# Sheet1.net
KiCad netlist of a schematic drawn in Altium Designer
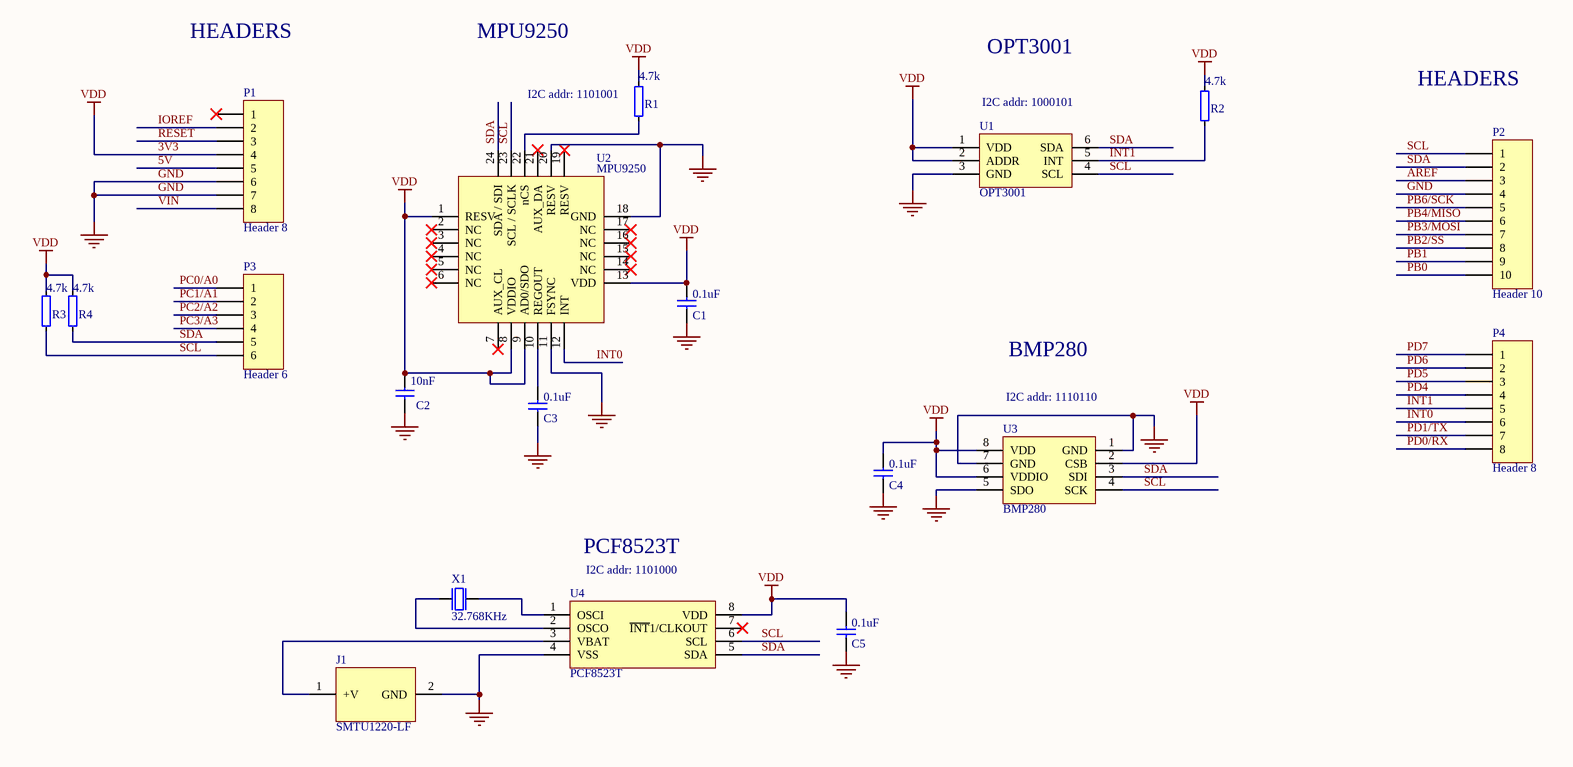
[diagram p0: Sheet1.SchDoc]

(export (version "E")
  (design (tool "Eeschema 10.0.6"))
  (components
    (comp (ref "C1") (value "0.1uF") (footprint "CAPC1608X06L") (libsource (lib "Schlib1") (part "CAP_0603")))
    (comp (ref "C2") (value "10nF") (footprint "CAPC1608X06L") (libsource (lib "Schlib1") (part "CAP_0603")))
    (comp (ref "C3") (value "0.1uF") (footprint "CAPC1608X06L") (libsource (lib "Schlib1") (part "CAP_0603")))
    (comp (ref "C4") (value "0.1uF") (footprint "CAPC1608X06L") (libsource (lib "Schlib1") (part "CAP_0603")))
    (comp (ref "C5") (value "0.1uF") (footprint "CAPC1608X06L") (libsource (lib "Schlib1") (part "CAP_0603")))
    (comp (ref "J1")
      (value "SMTU1220-LF")
      (footprint "SMTU1220-LF")
      (libsource (lib "Schlib1") (part "COIN_CELL"))
    )
    (comp (ref "P1")
      (value "Header 8")
      (footprint "HDR1X8")
      (description "Header, 8-Pin")
      (fields (field (name "PUBLISHER") "Altium Limited"))
      (libsource (lib "Miscellaneous Connectors") (part "Header 8"))
    )
    (comp (ref "P2")
      (value "Header 10")
      (footprint "HDR1X10")
      (description "Header, 10-Pin")
      (fields (field (name "PUBLISHER") "Altium Limited"))
      (libsource (lib "Miscellaneous Connectors") (part "Header 10"))
    )
    (comp (ref "P3")
      (value "Header 6")
      (footprint "HDR1X6")
      (description "Header, 6-Pin")
      (fields (field (name "PUBLISHER") "Altium Limited"))
      (libsource (lib "Miscellaneous Connectors") (part "Header 6"))
    )
    (comp (ref "P4")
      (value "Header 8")
      (footprint "HDR1X8")
      (description "Header, 8-Pin")
      (fields (field (name "PUBLISHER") "Altium Limited"))
      (libsource (lib "Miscellaneous Connectors") (part "Header 8"))
    )
    (comp (ref "R1") (value "4.7k") (footprint "RESC1608X06N") (libsource (lib "Schlib1") (part "RES_0603")))
    (comp (ref "R2") (value "4.7k") (footprint "RESC1608X06N") (libsource (lib "Schlib1") (part "RES_0603")))
    (comp (ref "R3") (value "4.7k") (footprint "RESC1608X06N") (libsource (lib "Schlib1") (part "RES_0603")))
    (comp (ref "R4") (value "4.7k") (footprint "RESC1608X06N") (libsource (lib "Schlib1") (part "RES_0603")))
    (comp (ref "U1")
      (value "OPT3001")
      (footprint "SON65P200X65_HS-7N")
      (libsource (lib "Schlib1") (part "OPT3001"))
    )
    (comp (ref "U2")
      (value "MPU9250")
      (footprint "QFN40P300X300X105_HS-25N")
      (libsource (lib "Schlib1") (part "MPU9250"))
    )
    (comp (ref "U3")
      (value "BMP280")
      (footprint "SON65P200X100-8N")
      (libsource (lib "Schlib1") (part "BMP280"))
    )
    (comp (ref "U4")
      (value "PCF8523T")
      (footprint "SOIC127P600X175-8N")
      (libsource (lib "Schlib1") (part "PCF8523T"))
    )
    (comp (ref "X1")
      (value "32.768KHz")
      (footprint "XTAL_3215")
      (description "32.768KHZ ±20PPM,9.0PF - CRYSTAL, SM, WATCH")
      (libsource (lib "Schlib1") (part "XTAL_3215"))
    )
  )
  (nets
    (net (code "1") (name "/5V") (class "Default")
      (node (ref "P1") (pin "5") (pinfunction "5_5") (pintype "passive"))
    )
    (net (code "2") (name "/AREF") (class "Default")
      (node (ref "P2") (pin "3") (pinfunction "3_3") (pintype "passive"))
    )
    (net (code "3") (name "/INT0") (class "Default")
      (node (ref "P4") (pin "6") (pinfunction "6_6") (pintype "passive"))
      (node (ref "U2") (pin "12") (pinfunction "INT_12") (pintype "passive"))
    )
    (net (code "4") (name "/INT1") (class "Default")
      (node (ref "P4") (pin "5") (pinfunction "5_5") (pintype "passive"))
      (node (ref "R2") (pin "1") (pinfunction "1_1") (pintype "passive"))
      (node (ref "U1") (pin "5") (pinfunction "INT_5") (pintype "passive"))
    )
    (net (code "5") (name "/IOREF") (class "Default")
      (node (ref "P1") (pin "2") (pinfunction "2_2") (pintype "passive"))
    )
    (net (code "6") (name "/PB0") (class "Default")
      (node (ref "P2") (pin "10") (pinfunction "10_10") (pintype "passive"))
    )
    (net (code "7") (name "/PB1") (class "Default")
      (node (ref "P2") (pin "9") (pinfunction "9_9") (pintype "passive"))
    )
    (net (code "8") (name "/PB2{slash}SS") (class "Default")
      (node (ref "P2") (pin "8") (pinfunction "8_8") (pintype "passive"))
    )
    (net (code "9") (name "/PB3{slash}MOSI") (class "Default")
      (node (ref "P2") (pin "7") (pinfunction "7_7") (pintype "passive"))
    )
    (net (code "10") (name "/PB4{slash}MISO") (class "Default")
      (node (ref "P2") (pin "6") (pinfunction "6_6") (pintype "passive"))
    )
    (net (code "11") (name "/PB6{slash}SCK") (class "Default")
      (node (ref "P2") (pin "5") (pinfunction "5_5") (pintype "passive"))
    )
    (net (code "12") (name "/PC0{slash}A0") (class "Default")
      (node (ref "P3") (pin "1") (pinfunction "1_1") (pintype "passive"))
    )
    (net (code "13") (name "/PC1{slash}A1") (class "Default")
      (node (ref "P3") (pin "2") (pinfunction "2_2") (pintype "passive"))
    )
    (net (code "14") (name "/PC2{slash}A2") (class "Default")
      (node (ref "P3") (pin "3") (pinfunction "3_3") (pintype "passive"))
    )
    (net (code "15") (name "/PC3{slash}A3") (class "Default")
      (node (ref "P3") (pin "4") (pinfunction "4_4") (pintype "passive"))
    )
    (net (code "16") (name "/PD0{slash}RX") (class "Default")
      (node (ref "P4") (pin "8") (pinfunction "8_8") (pintype "passive"))
    )
    (net (code "17") (name "/PD1{slash}TX") (class "Default")
      (node (ref "P4") (pin "7") (pinfunction "7_7") (pintype "passive"))
    )
    (net (code "18") (name "/PD4") (class "Default")
      (node (ref "P4") (pin "4") (pinfunction "4_4") (pintype "passive"))
    )
    (net (code "19") (name "/PD5") (class "Default")
      (node (ref "P4") (pin "3") (pinfunction "3_3") (pintype "passive"))
    )
    (net (code "20") (name "/PD6") (class "Default")
      (node (ref "P4") (pin "2") (pinfunction "2_2") (pintype "passive"))
    )
    (net (code "21") (name "/PD7") (class "Default")
      (node (ref "P4") (pin "1") (pinfunction "1_1") (pintype "passive"))
    )
    (net (code "22") (name "/RESET") (class "Default")
      (node (ref "P1") (pin "3") (pinfunction "3_3") (pintype "passive"))
    )
    (net (code "23") (name "/SCL") (class "Default")
      (node (ref "P2") (pin "1") (pinfunction "1_1") (pintype "passive"))
      (node (ref "P3") (pin "6") (pinfunction "6_6") (pintype "passive"))
      (node (ref "R3") (pin "1") (pinfunction "1_1") (pintype "passive"))
      (node (ref "U1") (pin "4") (pinfunction "SCL_4") (pintype "passive"))
      (node (ref "U2") (pin "23") (pinfunction "SCL_/_SCLK_23") (pintype "passive"))
      (node (ref "U3") (pin "4") (pinfunction "SCK_4") (pintype "passive"))
      (node (ref "U4") (pin "6") (pinfunction "SCL_6") (pintype "passive"))
    )
    (net (code "24") (name "/SDA") (class "Default")
      (node (ref "P2") (pin "2") (pinfunction "2_2") (pintype "passive"))
      (node (ref "P3") (pin "5") (pinfunction "5_5") (pintype "passive"))
      (node (ref "R4") (pin "1") (pinfunction "1_1") (pintype "passive"))
      (node (ref "U1") (pin "6") (pinfunction "SDA_6") (pintype "passive"))
      (node (ref "U2") (pin "24") (pinfunction "SDA_/_SDI_24") (pintype "passive"))
      (node (ref "U3") (pin "3") (pinfunction "SDI_3") (pintype "passive"))
      (node (ref "U4") (pin "5") (pinfunction "SDA_5") (pintype "passive"))
    )
    (net (code "25") (name "/VIN") (class "Default")
      (node (ref "P1") (pin "8") (pinfunction "8_8") (pintype "passive"))
    )
    (net (code "26") (name "GND") (class "Default")
      (node (ref "C1") (pin "1") (pinfunction "1_1") (pintype "passive"))
      (node (ref "C2") (pin "1") (pinfunction "1_1") (pintype "passive"))
      (node (ref "C3") (pin "1") (pinfunction "1_1") (pintype "passive"))
      (node (ref "C4") (pin "1") (pinfunction "1_1") (pintype "passive"))
      (node (ref "C5") (pin "1") (pinfunction "1_1") (pintype "passive"))
      (node (ref "J1") (pin "2") (pinfunction "GND_2") (pintype "passive"))
      (node (ref "P1") (pin "6") (pinfunction "6_6") (pintype "passive"))
      (node (ref "P1") (pin "7") (pinfunction "7_7") (pintype "passive"))
      (node (ref "P2") (pin "4") (pinfunction "4_4") (pintype "passive"))
      (node (ref "U1") (pin "3") (pinfunction "GND_3") (pintype "passive"))
      (node (ref "U2") (pin "11") (pinfunction "FSYNC_11") (pintype "passive"))
      (node (ref "U2") (pin "18") (pinfunction "GND_18") (pintype "passive"))
      (node (ref "U2") (pin "20") (pinfunction "RESV_20") (pintype "passive"))
      (node (ref "U3") (pin "1") (pinfunction "GND_1") (pintype "passive"))
      (node (ref "U3") (pin "5") (pinfunction "SDO_5") (pintype "passive"))
      (node (ref "U3") (pin "7") (pinfunction "GND_7") (pintype "passive"))
      (node (ref "U4") (pin "4") (pinfunction "VSS_4") (pintype "passive"))
    )
    (net (code "27") (name "Net-(J1-+V)") (class "Default")
      (node (ref "J1") (pin "1") (pinfunction "+V_1") (pintype "passive"))
      (node (ref "U4") (pin "3") (pinfunction "VBAT_3") (pintype "passive"))
    )
    (net (code "28") (name "Net-(U2-REGOUT)") (class "Default")
      (node (ref "C3") (pin "2") (pinfunction "2_2") (pintype "passive"))
      (node (ref "U2") (pin "10") (pinfunction "REGOUT_10") (pintype "passive"))
    )
    (net (code "29") (name "Net-(U2-nCS)") (class "Default")
      (node (ref "R1") (pin "1") (pinfunction "1_1") (pintype "passive"))
      (node (ref "U2") (pin "22") (pinfunction "nCS_22") (pintype "passive"))
    )
    (net (code "30") (name "Net-(U4-OSCI)") (class "Default")
      (node (ref "U4") (pin "1") (pinfunction "OSCI_1") (pintype "passive"))
      (node (ref "X1") (pin "2") (pinfunction "out_2") (pintype "passive"))
    )
    (net (code "31") (name "Net-(U4-OSCO)") (class "Default")
      (node (ref "U4") (pin "2") (pinfunction "OSCO_2") (pintype "passive"))
      (node (ref "X1") (pin "1") (pinfunction "inp_1") (pintype "passive"))
    )
    (net (code "32") (name "VDD") (class "Default")
      (node (ref "C1") (pin "2") (pinfunction "2_2") (pintype "passive"))
      (node (ref "C2") (pin "2") (pinfunction "2_2") (pintype "passive"))
      (node (ref "C4") (pin "2") (pinfunction "2_2") (pintype "passive"))
      (node (ref "C5") (pin "2") (pinfunction "2_2") (pintype "passive"))
      (node (ref "P1") (pin "4") (pinfunction "4_4") (pintype "passive"))
      (node (ref "R1") (pin "2") (pinfunction "2_2") (pintype "passive"))
      (node (ref "R2") (pin "2") (pinfunction "2_2") (pintype "passive"))
      (node (ref "R3") (pin "2") (pinfunction "2_2") (pintype "passive"))
      (node (ref "R4") (pin "2") (pinfunction "2_2") (pintype "passive"))
      (node (ref "U1") (pin "1") (pinfunction "VDD_1") (pintype "passive"))
      (node (ref "U1") (pin "2") (pinfunction "ADDR_2") (pintype "passive"))
      (node (ref "U2") (pin "1") (pinfunction "RESV_1") (pintype "passive"))
      (node (ref "U2") (pin "13") (pinfunction "VDD_13") (pintype "passive"))
      (node (ref "U2") (pin "8") (pinfunction "VDDIO_8") (pintype "passive"))
      (node (ref "U2") (pin "9") (pinfunction "AD0/SDO_9") (pintype "passive"))
      (node (ref "U3") (pin "2") (pinfunction "CSB_2") (pintype "passive"))
      (node (ref "U3") (pin "6") (pinfunction "VDDIO_6") (pintype "passive"))
      (node (ref "U3") (pin "8") (pinfunction "VDD_8") (pintype "passive"))
      (node (ref "U4") (pin "8") (pinfunction "VDD_8") (pintype "passive"))
    )
    (net (code "33") (name "unconnected-(P1-Pad1)") (class "Default")
      (node (ref "P1") (pin "1") (pinfunction "1_1") (pintype "passive+no_connect"))
    )
    (net (code "34") (name "unconnected-(U2-AUX_CL-Pad7)") (class "Default")
      (node (ref "U2") (pin "7") (pinfunction "AUX_CL_7") (pintype "passive+no_connect"))
    )
    (net (code "35") (name "unconnected-(U2-AUX_DA-Pad21)") (class "Default")
      (node (ref "U2") (pin "21") (pinfunction "AUX_DA_21") (pintype "passive+no_connect"))
    )
    (net (code "36") (name "unconnected-(U2-NC-Pad2)") (class "Default")
      (node (ref "U2") (pin "2") (pinfunction "NC_2") (pintype "passive+no_connect"))
    )
    (net (code "37") (name "unconnected-(U2-NC-Pad3)") (class "Default")
      (node (ref "U2") (pin "3") (pinfunction "NC_3") (pintype "passive+no_connect"))
    )
    (net (code "38") (name "unconnected-(U2-NC-Pad4)") (class "Default")
      (node (ref "U2") (pin "4") (pinfunction "NC_4") (pintype "passive+no_connect"))
    )
    (net (code "39") (name "unconnected-(U2-NC-Pad5)") (class "Default")
      (node (ref "U2") (pin "5") (pinfunction "NC_5") (pintype "passive+no_connect"))
    )
    (net (code "40") (name "unconnected-(U2-NC-Pad6)") (class "Default")
      (node (ref "U2") (pin "6") (pinfunction "NC_6") (pintype "passive+no_connect"))
    )
    (net (code "41") (name "unconnected-(U2-NC-Pad14)") (class "Default")
      (node (ref "U2") (pin "14") (pinfunction "NC_14") (pintype "passive+no_connect"))
    )
    (net (code "42") (name "unconnected-(U2-NC-Pad15)") (class "Default")
      (node (ref "U2") (pin "15") (pinfunction "NC_15") (pintype "passive+no_connect"))
    )
    (net (code "43") (name "unconnected-(U2-NC-Pad16)") (class "Default")
      (node (ref "U2") (pin "16") (pinfunction "NC_16") (pintype "passive+no_connect"))
    )
    (net (code "44") (name "unconnected-(U2-NC-Pad17)") (class "Default")
      (node (ref "U2") (pin "17") (pinfunction "NC_17") (pintype "passive+no_connect"))
    )
    (net (code "45") (name "unconnected-(U2-RESV-Pad19)") (class "Default")
      (node (ref "U2") (pin "19") (pinfunction "RESV_19") (pintype "passive+no_connect"))
    )
    (net (code "46") (name "unconnected-(U4-~{INT}1{slash}CLKOUT-Pad7)") (class "Default")
      (node (ref "U4") (pin "7") (pinfunction "~{INT}1/CLKOUT_7") (pintype "passive+no_connect"))
    )
  )
)
